# Light_and_Proximity_Sensor.net
KiCad netlist of a schematic drawn in Altium Designer
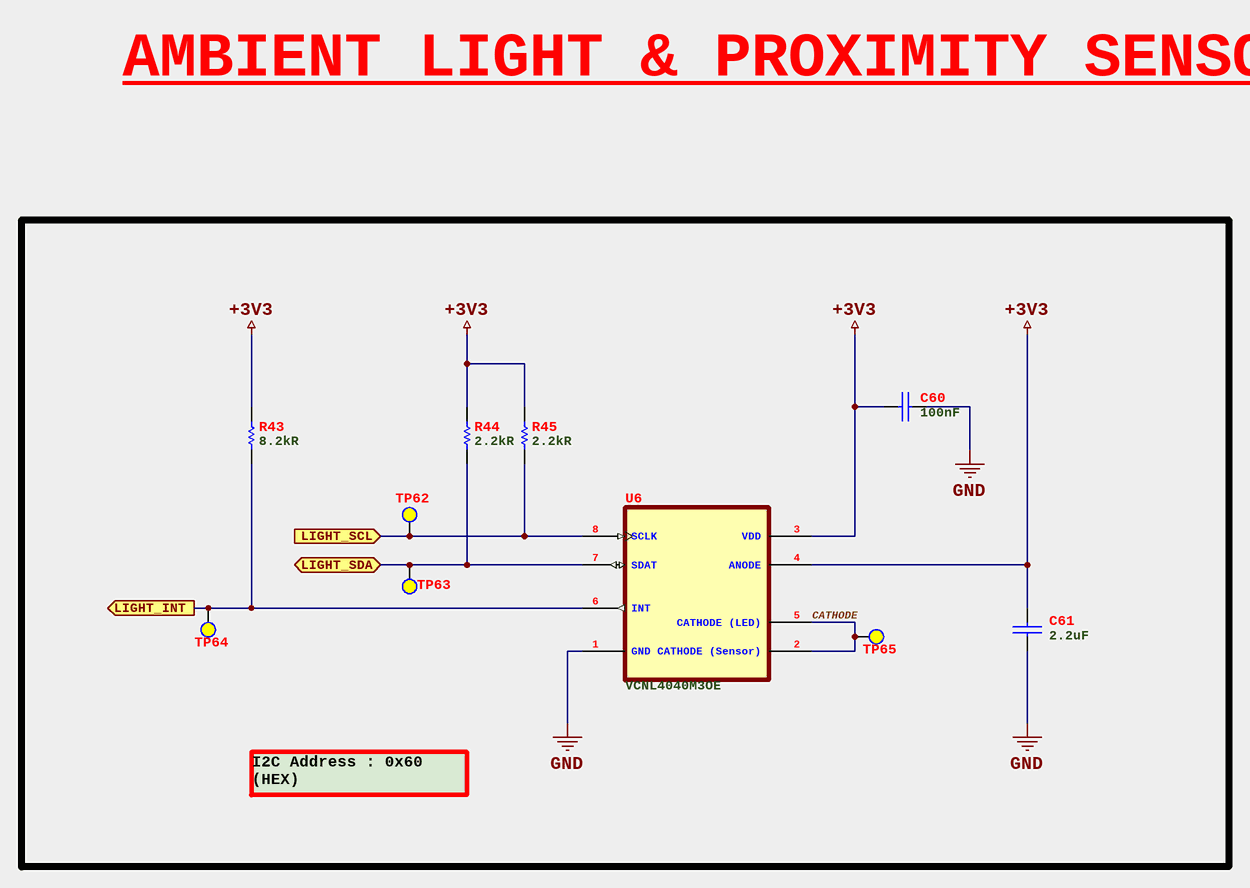
[diagram p0: Light and Proximity Sensor.SchDoc]

(export (version "E")
  (design (tool "Eeschema 10.0.6"))
  (components
    (comp (ref "C60")
      (value "100nF")
      (footprint "CAP_0603")
      (description "0.1 µF ±10% 50V Ceramic Capacitor X7R 0603 (1608 Metric)")
      (fields
        (field (name "MANUFACTURER") "Yageo")
        (field (name "MANUFACTURER PART NUMBER") "CC0603KRX7R9BB104")
      )
      (libsource (lib "Cellar Watchdog") (part "CAP_0.1uF-50V-10%_0603"))
    )
    (comp (ref "C61")
      (value "2.2uF")
      (footprint "CAP_0805")
      (description "2.2 µF ±10% 16V Ceramic Capacitor X7R 0805 (2012 Metric)")
      (fields
        (field (name "MANUFACTURER") "Yageo")
        (field (name "MANUFACTURER PART NUMBER") "CC0805KKX7R7BB225")
      )
      (libsource (lib "Cellar Watchdog") (part "CAP_2.2uF-16V-10%_0805"))
    )
    (comp (ref "R43")
      (value "8.2kR")
      (footprint "RES_0603")
      (description "8.2 kOhms ±1% 0.1W, 1/10W Chip Resistor 0603 (1608 Metric) Moisture Resistant Thick Film")
      (fields
        (field (name "MANUFACTURER") "Yageo")
        (field (name "MANUFACTURER PART NUMBER") "RC0603FR-078K2L")
      )
      (libsource (lib "Cellar Watchdog") (part "RES_8.2kR-100mW-1%_0603"))
    )
    (comp (ref "R44")
      (value "2.2kR")
      (footprint "RES_0603")
      (description "2.2 kOhms ±1% 0.1W, 1/10W Chip Resistor 0603 (1608 Metric) Moisture Resistant Thick Film")
      (fields
        (field (name "MANUFACTURER") "Yageo")
        (field (name "MANUFACTURER PART NUMBER") "RC0603FR-072K2L")
      )
      (libsource (lib "Cellar Watchdog") (part "RES_2.2kR-100mW-1%_0603"))
    )
    (comp (ref "R45")
      (value "2.2kR")
      (footprint "RES_0603")
      (description "2.2 kOhms ±1% 0.1W, 1/10W Chip Resistor 0603 (1608 Metric) Moisture Resistant Thick Film")
      (fields
        (field (name "MANUFACTURER") "Yageo")
        (field (name "MANUFACTURER PART NUMBER") "RC0603FR-072K2L")
      )
      (libsource (lib "Cellar Watchdog") (part "RES_2.2kR-100mW-1%_0603"))
    )
    (comp (ref "TP62")
      (value "LIGHT_SCL")
      (footprint "TEST POINT PAD")
      (description "PCB Test Point")
      (libsource (lib "Cellar Watchdog") (part "Test Point"))
    )
    (comp (ref "TP63")
      (value "LIGHT_SDA")
      (footprint "TEST POINT PAD")
      (description "PCB Test Point")
      (libsource (lib "Cellar Watchdog") (part "Test Point"))
    )
    (comp (ref "TP64")
      (value "LIGHT_INT")
      (footprint "TEST POINT PAD")
      (description "PCB Test Point")
      (libsource (lib "Cellar Watchdog") (part "Test Point"))
    )
    (comp (ref "TP65")
      (value "CATHODE")
      (footprint "TEST POINT PAD")
      (description "PCB Test Point")
      (libsource (lib "Cellar Watchdog") (part "Test Point"))
    )
    (comp (ref "U6")
      (value "VCNL4040M3OE")
      (footprint "IC_VISHAY_VCNL4040_4X2X1.1")
      (description "Optical Sensor Ambient 550nm I²C 8-SMD Module")
      (fields (field (name "MANUFACTURER") "Vishay Semiconductors"))
      (libsource (lib "Cellar Watchdog") (part "IC_VCNL4040M3OE"))
    )
  )
  (nets
    (net (code "1") (name "+3V3") (class "Default")
      (node (ref "C60") (pin "1") (pinfunction "1_1") (pintype "passive"))
      (node (ref "C61") (pin "1") (pinfunction "1_1") (pintype "passive"))
      (node (ref "R43") (pin "2") (pinfunction "2_2") (pintype "passive"))
      (node (ref "R44") (pin "2") (pinfunction "2_2") (pintype "passive"))
      (node (ref "R45") (pin "2") (pinfunction "2_2") (pintype "passive"))
      (node (ref "U6") (pin "3") (pinfunction "VDD_3") (pintype "power_in"))
      (node (ref "U6") (pin "4") (pinfunction "ANODE_4") (pintype "power_in"))
    )
    (net (code "2") (name "/CATHODE") (class "Default")
      (node (ref "TP65") (pin "TP") (pinfunction "TP_TP") (pintype "passive"))
      (node (ref "U6") (pin "2") (pinfunction "CATHODE_(Sensor)_2") (pintype "power_in"))
      (node (ref "U6") (pin "5") (pinfunction "CATHODE_(LED)_5") (pintype "power_in"))
    )
    (net (code "3") (name "/LIGHT_INT") (class "Default")
      (node (ref "R43") (pin "1") (pinfunction "1_1") (pintype "passive"))
      (node (ref "TP64") (pin "TP") (pinfunction "TP_TP") (pintype "passive"))
      (node (ref "U6") (pin "6") (pinfunction "INT_6") (pintype "output"))
    )
    (net (code "4") (name "/LIGHT_SCL") (class "Default")
      (node (ref "R45") (pin "1") (pinfunction "1_1") (pintype "passive"))
      (node (ref "TP62") (pin "TP") (pinfunction "TP_TP") (pintype "passive"))
      (node (ref "U6") (pin "8") (pinfunction "SCLK_8") (pintype "input"))
    )
    (net (code "5") (name "/LIGHT_SDA") (class "Default")
      (node (ref "R44") (pin "1") (pinfunction "1_1") (pintype "passive"))
      (node (ref "TP63") (pin "TP") (pinfunction "TP_TP") (pintype "passive"))
      (node (ref "U6") (pin "7") (pinfunction "SDAT_7") (pintype "bidirectional"))
    )
    (net (code "6") (name "GND") (class "Default")
      (node (ref "C60") (pin "2") (pinfunction "2_2") (pintype "passive"))
      (node (ref "C61") (pin "2") (pinfunction "2_2") (pintype "passive"))
      (node (ref "U6") (pin "1") (pinfunction "GND_1") (pintype "power_in"))
    )
  )
)
